# esquematico.net
KiCad netlist of a schematic drawn in Altium Designer
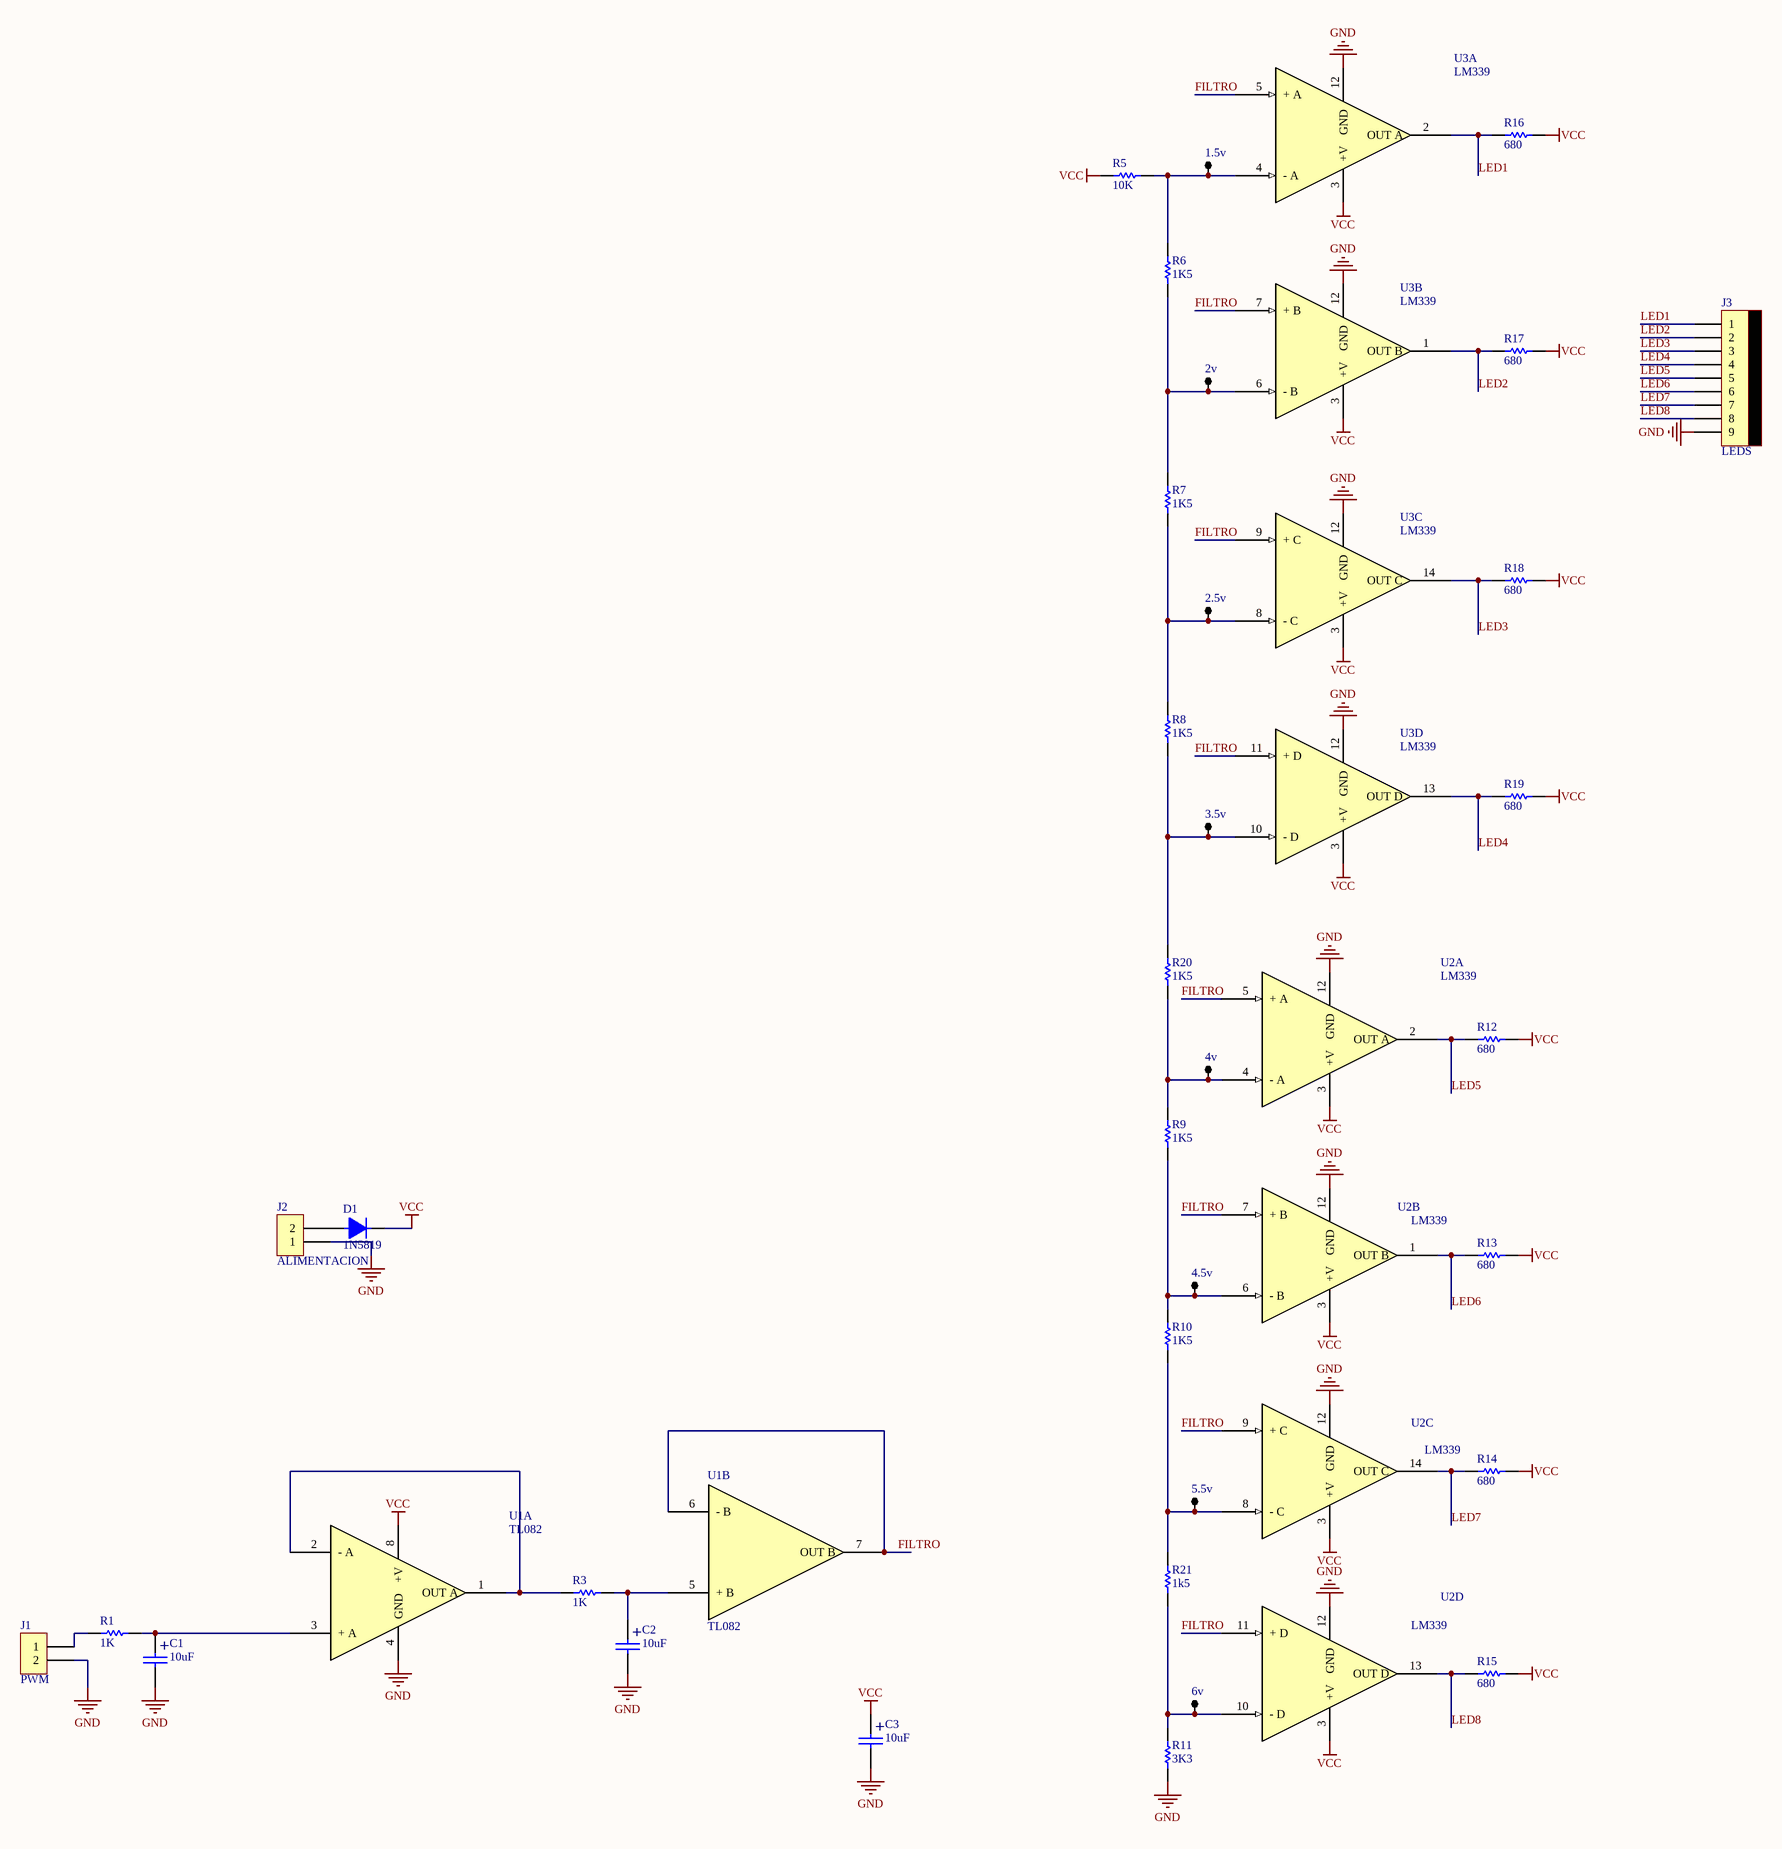
[diagram p0: esquematico.SchDoc]

(export (version "E")
  (design (tool "Eeschema 10.0.6"))
  (components
    (comp (ref "1.5v") (value "~") (footprint "TPTH") (libsource (lib "LIBEBAL") (part "TP")))
    (comp (ref "2.5v") (value "~") (footprint "TPTH") (libsource (lib "LIBEBAL") (part "TP")))
    (comp (ref "2v") (value "~") (footprint "TPTH") (libsource (lib "LIBEBAL") (part "TP")))
    (comp (ref "3.5v") (value "~") (footprint "TPTH") (libsource (lib "LIBEBAL") (part "TP")))
    (comp (ref "4.5v") (value "~") (footprint "TPTH") (libsource (lib "LIBEBAL") (part "TP")))
    (comp (ref "4v") (value "~") (footprint "TPTH") (libsource (lib "LIBEBAL") (part "TP")))
    (comp (ref "5.5v") (value "~") (footprint "TPTH") (libsource (lib "LIBEBAL") (part "TP")))
    (comp (ref "6v") (value "~") (footprint "TPTH") (libsource (lib "LIBEBAL") (part "TP")))
    (comp (ref "C1") (value "10uF") (footprint "CAP100RP") (libsource (lib "LIB-PIO-IX") (part "CAPPOL")))
    (comp (ref "C2") (value "10uF") (footprint "CAP100RP") (libsource (lib "LIB-PIO-IX") (part "CAPPOL")))
    (comp (ref "C3") (value "10uF") (footprint "CAP100RP") (libsource (lib "LIB-PIO-IX") (part "CAPPOL")))
    (comp (ref "D1") (value "1N5819") (footprint "DO41") (libsource (lib "LIBPIOIX 0314A") (part "DIODO")))
    (comp (ref "J1") (value "PWM") (footprint "BORNERA2") (libsource (lib "") (part "BORNERA 2_1")))
    (comp (ref "J2")
      (value "ALIMENTACION")
      (footprint "BORNERA2")
      (libsource (lib "LIBPIOIX") (part "BORNERA 2"))
    )
    (comp (ref "J3") (value "LEDS") (footprint "MOLEX9") (libsource (lib "LIBEBAL") (part "MOLEX9")))
    (comp (ref "R1") (value "1K") (footprint "RES400") (libsource (lib "LIBEBAL") (part "RES")))
    (comp (ref "R3") (value "1K") (footprint "RES400") (libsource (lib "LIBEBAL") (part "RES")))
    (comp (ref "R5") (value "10K") (footprint "RES400") (libsource (lib "LIBEBAL") (part "RES")))
    (comp (ref "R6") (value "1K5") (footprint "RES400") (libsource (lib "LIBEBAL") (part "RES")))
    (comp (ref "R7") (value "1K5") (footprint "RES400") (libsource (lib "LIBEBAL") (part "RES")))
    (comp (ref "R8") (value "1K5") (footprint "RES400") (libsource (lib "LIBEBAL") (part "RES")))
    (comp (ref "R9") (value "1K5") (footprint "RES400") (libsource (lib "LIBEBAL") (part "RES")))
    (comp (ref "R10") (value "1K5") (footprint "RES400") (libsource (lib "LIBEBAL") (part "RES")))
    (comp (ref "R11") (value "3K3") (footprint "RES400") (libsource (lib "LIBEBAL") (part "RES")))
    (comp (ref "R12") (value "680") (footprint "RES400") (libsource (lib "LIBEBAL") (part "RES")))
    (comp (ref "R13") (value "680") (footprint "RES400") (libsource (lib "LIBEBAL") (part "RES")))
    (comp (ref "R14") (value "680") (footprint "RES400") (libsource (lib "LIBEBAL") (part "RES")))
    (comp (ref "R15") (value "680") (footprint "RES400") (libsource (lib "LIBEBAL") (part "RES")))
    (comp (ref "R16") (value "680") (footprint "RES400") (libsource (lib "LIBEBAL") (part "RES")))
    (comp (ref "R17") (value "680") (footprint "RES400") (libsource (lib "LIBEBAL") (part "RES")))
    (comp (ref "R18") (value "680") (footprint "RES400") (libsource (lib "LIBEBAL") (part "RES")))
    (comp (ref "R19") (value "680") (footprint "RES400") (libsource (lib "LIBEBAL") (part "RES")))
    (comp (ref "R20") (value "1K5") (footprint "RES400") (libsource (lib "LIB-PIO-IX") (part "RES")))
    (comp (ref "R21") (value "1k5") (footprint "RES400") (libsource (lib "LIB-PIO-IX") (part "RES")))
    (comp (ref "U1")
      (value "TL082")
      (footprint "DIP8")
      (libsource (lib "Libreria Buena Onda V2") (part "TL082"))
    )
    (comp (ref "U2")
      (value "LM339")
      (footprint "DIP14")
      (description "Comparador Open Collector")
      (libsource (lib "Libreria4") (part "LM339"))
    )
    (comp (ref "U3")
      (value "LM339")
      (footprint "DIP14")
      (description "Comparador Open Collector")
      (libsource (lib "Libreria4") (part "LM339"))
    )
  )
  (nets
    (net (code "1") (name "/FILTRO") (class "Default")
      (node (ref "U1") (pin "6") (pinfunction "-_B_6") (pintype "passive"))
      (node (ref "U1") (pin "7") (pinfunction "OUT_B_7") (pintype "passive"))
      (node (ref "U2") (pin "11") (pinfunction "+_D_11") (pintype "input"))
      (node (ref "U2") (pin "5") (pinfunction "+_A_5") (pintype "input"))
      (node (ref "U2") (pin "7") (pinfunction "+_B_7") (pintype "input"))
      (node (ref "U2") (pin "9") (pinfunction "+_C_9") (pintype "input"))
      (node (ref "U3") (pin "11") (pinfunction "+_D_11") (pintype "input"))
      (node (ref "U3") (pin "5") (pinfunction "+_A_5") (pintype "input"))
      (node (ref "U3") (pin "7") (pinfunction "+_B_7") (pintype "input"))
      (node (ref "U3") (pin "9") (pinfunction "+_C_9") (pintype "input"))
    )
    (net (code "2") (name "/LED1") (class "Default")
      (node (ref "J3") (pin "1") (pinfunction "1_1") (pintype "passive"))
      (node (ref "R16") (pin "1") (pinfunction "1_1") (pintype "passive"))
      (node (ref "U3") (pin "2") (pinfunction "OUT_A_2") (pintype "open_collector"))
    )
    (net (code "3") (name "/LED2") (class "Default")
      (node (ref "J3") (pin "2") (pinfunction "2_2") (pintype "passive"))
      (node (ref "R17") (pin "1") (pinfunction "1_1") (pintype "passive"))
      (node (ref "U3") (pin "1") (pinfunction "OUT_B_1") (pintype "open_collector"))
    )
    (net (code "4") (name "/LED3") (class "Default")
      (node (ref "J3") (pin "3") (pinfunction "3_3") (pintype "passive"))
      (node (ref "R18") (pin "1") (pinfunction "1_1") (pintype "passive"))
      (node (ref "U3") (pin "14") (pinfunction "OUT_C_14") (pintype "open_collector"))
    )
    (net (code "5") (name "/LED4") (class "Default")
      (node (ref "J3") (pin "4") (pinfunction "4_4") (pintype "passive"))
      (node (ref "R19") (pin "1") (pinfunction "1_1") (pintype "passive"))
      (node (ref "U3") (pin "13") (pinfunction "OUT_D_13") (pintype "open_collector"))
    )
    (net (code "6") (name "/LED5") (class "Default")
      (node (ref "J3") (pin "5") (pinfunction "5_5") (pintype "passive"))
      (node (ref "R12") (pin "1") (pinfunction "1_1") (pintype "passive"))
      (node (ref "U2") (pin "2") (pinfunction "OUT_A_2") (pintype "open_collector"))
    )
    (net (code "7") (name "/LED6") (class "Default")
      (node (ref "J3") (pin "6") (pinfunction "6_6") (pintype "passive"))
      (node (ref "R13") (pin "1") (pinfunction "1_1") (pintype "passive"))
      (node (ref "U2") (pin "1") (pinfunction "OUT_B_1") (pintype "open_collector"))
    )
    (net (code "8") (name "/LED7") (class "Default")
      (node (ref "J3") (pin "7") (pinfunction "7_7") (pintype "passive"))
      (node (ref "R14") (pin "1") (pinfunction "1_1") (pintype "passive"))
      (node (ref "U2") (pin "14") (pinfunction "OUT_C_14") (pintype "open_collector"))
    )
    (net (code "9") (name "/LED8") (class "Default")
      (node (ref "J3") (pin "8") (pinfunction "8_8") (pintype "passive"))
      (node (ref "R15") (pin "1") (pinfunction "1_1") (pintype "passive"))
      (node (ref "U2") (pin "13") (pinfunction "OUT_D_13") (pintype "open_collector"))
    )
    (net (code "10") (name "GND") (class "Default")
      (node (ref "C1") (pin "2") (pinfunction "2_2") (pintype "passive"))
      (node (ref "C2") (pin "2") (pinfunction "2_2") (pintype "passive"))
      (node (ref "C3") (pin "2") (pinfunction "2_2") (pintype "passive"))
      (node (ref "J1") (pin "2") (pinfunction "2_2") (pintype "passive"))
      (node (ref "J2") (pin "1") (pinfunction "1_1") (pintype "passive"))
      (node (ref "J3") (pin "9") (pinfunction "9_9") (pintype "passive"))
      (node (ref "R11") (pin "1") (pinfunction "1_1") (pintype "passive"))
      (node (ref "U1") (pin "4") (pinfunction "GND_4") (pintype "passive"))
      (node (ref "U2") (pin "12") (pinfunction "GND_12") (pintype "passive"))
      (node (ref "U3") (pin "12") (pinfunction "GND_12") (pintype "passive"))
    )
    (net (code "11") (name "Net-(D1-Pad1)") (class "Default")
      (node (ref "D1") (pin "1") (pinfunction "1_1") (pintype "passive"))
      (node (ref "J2") (pin "2") (pinfunction "2_2") (pintype "passive"))
    )
    (net (code "12") (name "Net-(J1-Pad1)") (class "Default")
      (node (ref "J1") (pin "1") (pinfunction "1_1") (pintype "passive"))
      (node (ref "R1") (pin "1") (pinfunction "1_1") (pintype "passive"))
    )
    (net (code "13") (name "Net-(U1A-+_A)") (class "Default")
      (node (ref "C1") (pin "1") (pinfunction "1_1") (pintype "passive"))
      (node (ref "R1") (pin "2") (pinfunction "2_2") (pintype "passive"))
      (node (ref "U1") (pin "3") (pinfunction "+_A_3") (pintype "passive"))
    )
    (net (code "14") (name "Net-(U1A--_A)") (class "Default")
      (node (ref "R3") (pin "1") (pinfunction "1_1") (pintype "passive"))
      (node (ref "U1") (pin "1") (pinfunction "OUT_A_1") (pintype "passive"))
      (node (ref "U1") (pin "2") (pinfunction "-_A_2") (pintype "passive"))
    )
    (net (code "15") (name "Net-(U1B-+_B)") (class "Default")
      (node (ref "C2") (pin "1") (pinfunction "1_1") (pintype "passive"))
      (node (ref "R3") (pin "2") (pinfunction "2_2") (pintype "passive"))
      (node (ref "U1") (pin "5") (pinfunction "+_B_5") (pintype "passive"))
    )
    (net (code "16") (name "Net-(U2A--_A)") (class "Default")
      (node (ref "4v") (pin "1") (pinfunction "1_1") (pintype "passive"))
      (node (ref "R20") (pin "1") (pinfunction "1_1") (pintype "passive"))
      (node (ref "R9") (pin "2") (pinfunction "2_2") (pintype "passive"))
      (node (ref "U2") (pin "4") (pinfunction "-_A_4") (pintype "input"))
    )
    (net (code "17") (name "Net-(U2B--_B)") (class "Default")
      (node (ref "4.5v") (pin "1") (pinfunction "1_1") (pintype "passive"))
      (node (ref "R10") (pin "2") (pinfunction "2_2") (pintype "passive"))
      (node (ref "R9") (pin "1") (pinfunction "1_1") (pintype "passive"))
      (node (ref "U2") (pin "6") (pinfunction "-_B_6") (pintype "input"))
    )
    (net (code "18") (name "Net-(U2C--_C)") (class "Default")
      (node (ref "5.5v") (pin "1") (pinfunction "1_1") (pintype "passive"))
      (node (ref "R10") (pin "1") (pinfunction "1_1") (pintype "passive"))
      (node (ref "R21") (pin "2") (pinfunction "2_2") (pintype "passive"))
      (node (ref "U2") (pin "8") (pinfunction "-_C_8") (pintype "input"))
    )
    (net (code "19") (name "Net-(U2D--_D)") (class "Default")
      (node (ref "6v") (pin "1") (pinfunction "1_1") (pintype "passive"))
      (node (ref "R11") (pin "2") (pinfunction "2_2") (pintype "passive"))
      (node (ref "R21") (pin "1") (pinfunction "1_1") (pintype "passive"))
      (node (ref "U2") (pin "10") (pinfunction "-_D_10") (pintype "input"))
    )
    (net (code "20") (name "Net-(U3A--_A)") (class "Default")
      (node (ref "1.5v") (pin "1") (pinfunction "1_1") (pintype "passive"))
      (node (ref "R5") (pin "2") (pinfunction "2_2") (pintype "passive"))
      (node (ref "R6") (pin "2") (pinfunction "2_2") (pintype "passive"))
      (node (ref "U3") (pin "4") (pinfunction "-_A_4") (pintype "input"))
    )
    (net (code "21") (name "Net-(U3B--_B)") (class "Default")
      (node (ref "2v") (pin "1") (pinfunction "1_1") (pintype "passive"))
      (node (ref "R6") (pin "1") (pinfunction "1_1") (pintype "passive"))
      (node (ref "R7") (pin "2") (pinfunction "2_2") (pintype "passive"))
      (node (ref "U3") (pin "6") (pinfunction "-_B_6") (pintype "input"))
    )
    (net (code "22") (name "Net-(U3C--_C)") (class "Default")
      (node (ref "2.5v") (pin "1") (pinfunction "1_1") (pintype "passive"))
      (node (ref "R7") (pin "1") (pinfunction "1_1") (pintype "passive"))
      (node (ref "R8") (pin "2") (pinfunction "2_2") (pintype "passive"))
      (node (ref "U3") (pin "8") (pinfunction "-_C_8") (pintype "input"))
    )
    (net (code "23") (name "Net-(U3D--_D)") (class "Default")
      (node (ref "3.5v") (pin "1") (pinfunction "1_1") (pintype "passive"))
      (node (ref "R20") (pin "2") (pinfunction "2_2") (pintype "passive"))
      (node (ref "R8") (pin "1") (pinfunction "1_1") (pintype "passive"))
      (node (ref "U3") (pin "10") (pinfunction "-_D_10") (pintype "input"))
    )
    (net (code "24") (name "VCC") (class "Default")
      (node (ref "C3") (pin "1") (pinfunction "1_1") (pintype "passive"))
      (node (ref "D1") (pin "2") (pinfunction "2_2") (pintype "passive"))
      (node (ref "R12") (pin "2") (pinfunction "2_2") (pintype "passive"))
      (node (ref "R13") (pin "2") (pinfunction "2_2") (pintype "passive"))
      (node (ref "R14") (pin "2") (pinfunction "2_2") (pintype "passive"))
      (node (ref "R15") (pin "2") (pinfunction "2_2") (pintype "passive"))
      (node (ref "R16") (pin "2") (pinfunction "2_2") (pintype "passive"))
      (node (ref "R17") (pin "2") (pinfunction "2_2") (pintype "passive"))
      (node (ref "R18") (pin "2") (pinfunction "2_2") (pintype "passive"))
      (node (ref "R19") (pin "2") (pinfunction "2_2") (pintype "passive"))
      (node (ref "R5") (pin "1") (pinfunction "1_1") (pintype "passive"))
      (node (ref "U1") (pin "8") (pinfunction "+V_8") (pintype "passive"))
      (node (ref "U2") (pin "3") (pinfunction "+V_3") (pintype "passive"))
      (node (ref "U3") (pin "3") (pinfunction "+V_3") (pintype "passive"))
    )
  )
)
